# LedKeychain.net
KiCad netlist of a schematic drawn in EasyEDA Pro
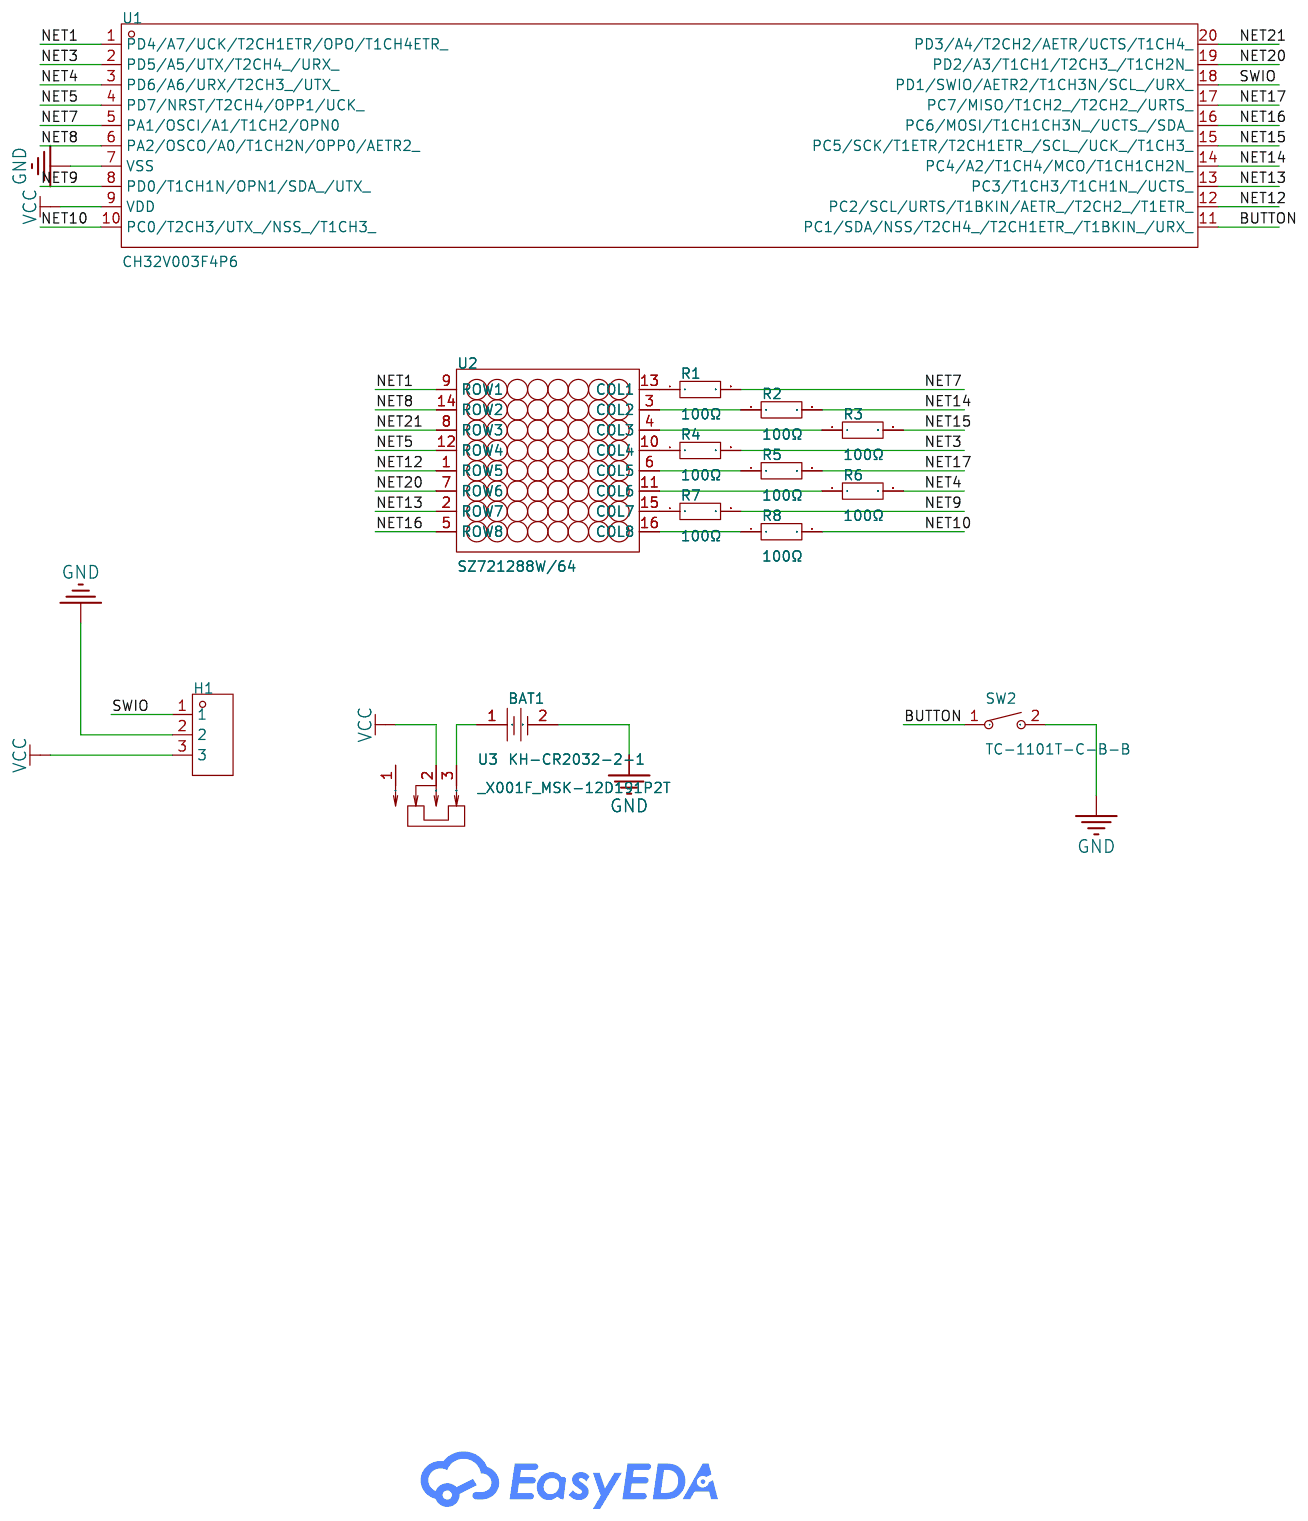
[diagram p0: schematic sheet]

(export (version "E")
  (design (tool "Eeschema 10.0.6"))
  (components
    (comp (ref "BAT1")
      (value "KH-CR2032-2-1")
      (footprint "easyedapro:BAT-TH_KH-CR2032-2-1")
      (fields (field (name "Manufacturer") "kinghelm(金航标)"))
      (libsource (lib "easyedapro") (part "KH-CR2032-2-1"))
    )
    (comp (ref "H1")
      (value "~")
      (footprint "easyedapro:HDR-TH_3P-P2.54-V-M")
      (libsource (lib "easyedapro") (part "PZ254V-11-03P_C2937625"))
    )
    (comp (ref "R1")
      (value "100Ω")
      (footprint "easyedapro:R0805")
      (fields
        (field (name "Manufacturer Part") "0805W8F1002T5E")
        (field (name "Manufacturer") "UNI-ROYAL(厚声)")
      )
      (libsource (lib "easyedapro") (part "0805W8F1002T5E"))
    )
    (comp (ref "R2")
      (value "100Ω")
      (footprint "easyedapro:R0805")
      (fields
        (field (name "Manufacturer Part") "0805W8F1002T5E")
        (field (name "Manufacturer") "UNI-ROYAL(厚声)")
      )
      (libsource (lib "easyedapro") (part "0805W8F1002T5E"))
    )
    (comp (ref "R3")
      (value "100Ω")
      (footprint "easyedapro:R0805")
      (fields
        (field (name "Manufacturer Part") "0805W8F1002T5E")
        (field (name "Manufacturer") "UNI-ROYAL(厚声)")
      )
      (libsource (lib "easyedapro") (part "0805W8F1002T5E"))
    )
    (comp (ref "R4")
      (value "100Ω")
      (footprint "easyedapro:R0805")
      (fields
        (field (name "Manufacturer Part") "0805W8F1002T5E")
        (field (name "Manufacturer") "UNI-ROYAL(厚声)")
      )
      (libsource (lib "easyedapro") (part "0805W8F1002T5E"))
    )
    (comp (ref "R5")
      (value "100Ω")
      (footprint "easyedapro:R0805")
      (fields
        (field (name "Manufacturer Part") "0805W8F1002T5E")
        (field (name "Manufacturer") "UNI-ROYAL(厚声)")
      )
      (libsource (lib "easyedapro") (part "0805W8F1002T5E"))
    )
    (comp (ref "R6")
      (value "100Ω")
      (footprint "easyedapro:R0805")
      (fields
        (field (name "Manufacturer Part") "0805W8F1002T5E")
        (field (name "Manufacturer") "UNI-ROYAL(厚声)")
      )
      (libsource (lib "easyedapro") (part "0805W8F1002T5E"))
    )
    (comp (ref "R7")
      (value "100Ω")
      (footprint "easyedapro:R0805")
      (fields
        (field (name "Manufacturer Part") "0805W8F1002T5E")
        (field (name "Manufacturer") "UNI-ROYAL(厚声)")
      )
      (libsource (lib "easyedapro") (part "0805W8F1002T5E"))
    )
    (comp (ref "R8")
      (value "100Ω")
      (footprint "easyedapro:R0805")
      (fields
        (field (name "Manufacturer Part") "0805W8F1002T5E")
        (field (name "Manufacturer") "UNI-ROYAL(厚声)")
      )
      (libsource (lib "easyedapro") (part "0805W8F1002T5E"))
    )
    (comp (ref "SW2")
      (value "TC-1101T-C-B-B")
      (footprint "easyedapro:KEY-TH_2P-L6.0-W3.5-P6.50")
      (fields (field (name "Manufacturer") "XKB Connectivity(中国星坤)"))
      (libsource (lib "easyedapro") (part "TC-1101T-C-B-B"))
    )
    (comp (ref "U1")
      (value "CH32V003F4P6")
      (footprint "easyedapro:TSSOP-20_L6.5-W4.4-P0.65-LS6.4-BL")
      (fields (field (name "Manufacturer") "WCH(南京沁恒)"))
      (libsource (lib "easyedapro") (part "CH32V003F4P6"))
    )
    (comp (ref "U2")
      (value "SZ721288W/64")
      (footprint "easyedapro:LED-SEG-TH_SZ421288N-64")
      (description "Dot Matrix Number:8x8 Emitting Color:White Polarity:Common Cathode")
      (fields (field (name "Manufacturer") "ARKLED(方舟)"))
      (libsource (lib "easyedapro") (part "SZ721288W/64"))
    )
    (comp (ref "U3")
      (value "_X001F_MSK-12D191P2T")
      (footprint "easyedapro:SW-TH_MSK-12D191P2T")
      (fields (field (name "Manufacturer Part") "_x001F_MSK-12D191P2T"))
      (libsource (lib "easyedapro") (part "MSK-12D19"))
    )
  )
  (nets
    (net (code "1") (name "/BUTTON") (class "Default")
      (node (ref "SW2") (pin "1") (pinfunction "1_1") (pintype "input"))
      (node (ref "U1") (pin "11") (pinfunction "PC1/SDA/NSS/T2CH4_/T2CH1ETR_/T1BKIN_/URX__11") (pintype "unspecified"))
    )
    (net (code "2") (name "/NET1") (class "Default")
      (node (ref "U1") (pin "1") (pinfunction "PD4/A7/UCK/T2CH1ETR/OPO/T1CH4ETR__1") (pintype "unspecified"))
      (node (ref "U2") (pin "9") (pinfunction "ROW1_9") (pintype "unspecified"))
    )
    (net (code "3") (name "/NET3") (class "Default")
      (node (ref "R4") (pin "2") (pinfunction "2_2") (pintype "input"))
      (node (ref "U1") (pin "2") (pinfunction "PD5/A5/UTX/T2CH4_/URX__2") (pintype "unspecified"))
    )
    (net (code "4") (name "/NET4") (class "Default")
      (node (ref "R6") (pin "2") (pinfunction "2_2") (pintype "input"))
      (node (ref "U1") (pin "3") (pinfunction "PD6/A6/URX/T2CH3_/UTX__3") (pintype "unspecified"))
    )
    (net (code "5") (name "/NET5") (class "Default")
      (node (ref "U1") (pin "4") (pinfunction "PD7/NRST/T2CH4/OPP1/UCK__4") (pintype "unspecified"))
      (node (ref "U2") (pin "12") (pinfunction "ROW4_12") (pintype "unspecified"))
    )
    (net (code "6") (name "/NET7") (class "Default")
      (node (ref "R1") (pin "2") (pinfunction "2_2") (pintype "input"))
      (node (ref "U1") (pin "5") (pinfunction "PA1/OSCI/A1/T1CH2/OPN0_5") (pintype "unspecified"))
    )
    (net (code "7") (name "/NET8") (class "Default")
      (node (ref "U1") (pin "6") (pinfunction "PA2/OSCO/A0/T1CH2N/OPP0/AETR2__6") (pintype "unspecified"))
      (node (ref "U2") (pin "14") (pinfunction "ROW2_14") (pintype "unspecified"))
    )
    (net (code "8") (name "/NET9") (class "Default")
      (node (ref "R7") (pin "2") (pinfunction "2_2") (pintype "input"))
      (node (ref "U1") (pin "8") (pinfunction "PD0/T1CH1N/OPN1/SDA_/UTX__8") (pintype "unspecified"))
    )
    (net (code "9") (name "/NET10") (class "Default")
      (node (ref "R8") (pin "2") (pinfunction "2_2") (pintype "input"))
      (node (ref "U1") (pin "10") (pinfunction "PC0/T2CH3/UTX_/NSS_/T1CH3__10") (pintype "unspecified"))
    )
    (net (code "10") (name "/NET12") (class "Default")
      (node (ref "U1") (pin "12") (pinfunction "PC2/SCL/URTS/T1BKIN/AETR_/T2CH2_/T1ETR__12") (pintype "unspecified"))
      (node (ref "U2") (pin "1") (pinfunction "ROW5_1") (pintype "unspecified"))
    )
    (net (code "11") (name "/NET13") (class "Default")
      (node (ref "U1") (pin "13") (pinfunction "PC3/T1CH3/T1CH1N_/UCTS__13") (pintype "unspecified"))
      (node (ref "U2") (pin "2") (pinfunction "ROW7_2") (pintype "unspecified"))
    )
    (net (code "12") (name "/NET14") (class "Default")
      (node (ref "R2") (pin "2") (pinfunction "2_2") (pintype "input"))
      (node (ref "U1") (pin "14") (pinfunction "PC4/A2/T1CH4/MCO/T1CH1CH2N__14") (pintype "unspecified"))
    )
    (net (code "13") (name "/NET15") (class "Default")
      (node (ref "R3") (pin "2") (pinfunction "2_2") (pintype "input"))
      (node (ref "U1") (pin "15") (pinfunction "PC5/SCK/T1ETR/T2CH1ETR_/SCL_/UCK_/T1CH3__15") (pintype "unspecified"))
    )
    (net (code "14") (name "/NET16") (class "Default")
      (node (ref "U1") (pin "16") (pinfunction "PC6/MOSI/T1CH1CH3N_/UCTS_/SDA__16") (pintype "unspecified"))
      (node (ref "U2") (pin "5") (pinfunction "ROW8_5") (pintype "unspecified"))
    )
    (net (code "15") (name "/NET17") (class "Default")
      (node (ref "R5") (pin "2") (pinfunction "2_2") (pintype "input"))
      (node (ref "U1") (pin "17") (pinfunction "PC7/MISO/T1CH2_/T2CH2_/URTS__17") (pintype "unspecified"))
    )
    (net (code "16") (name "/NET20") (class "Default")
      (node (ref "U1") (pin "19") (pinfunction "PD2/A3/T1CH1/T2CH3_/T1CH2N__19") (pintype "unspecified"))
      (node (ref "U2") (pin "7") (pinfunction "ROW6_7") (pintype "unspecified"))
    )
    (net (code "17") (name "/NET21") (class "Default")
      (node (ref "U1") (pin "20") (pinfunction "PD3/A4/T2CH2/AETR/UCTS/T1CH4__20") (pintype "unspecified"))
      (node (ref "U2") (pin "8") (pinfunction "ROW3_8") (pintype "unspecified"))
    )
    (net (code "18") (name "/SWIO") (class "Default")
      (node (ref "H1") (pin "1") (pinfunction "1_1") (pintype "unspecified"))
      (node (ref "U1") (pin "18") (pinfunction "PD1/SWIO/AETR2/T1CH3N/SCL_/URX__18") (pintype "unspecified"))
    )
    (net (code "19") (name "GND") (class "Default")
      (node (ref "BAT1") (pin "2") (pinfunction "2_2") (pintype "input"))
      (node (ref "H1") (pin "2") (pinfunction "2_2") (pintype "unspecified"))
      (node (ref "SW2") (pin "2") (pinfunction "2_2") (pintype "input"))
      (node (ref "U1") (pin "7") (pinfunction "VSS_7") (pintype "unspecified"))
    )
    (net (code "20") (name "Net-(BAT1-Pad1)") (class "Default")
      (node (ref "BAT1") (pin "1") (pinfunction "1_1") (pintype "input"))
      (node (ref "U3") (pin "3") (pinfunction "3_3") (pintype "unspecified"))
    )
    (net (code "21") (name "Net-(U2-COL1)") (class "Default")
      (node (ref "R1") (pin "1") (pinfunction "1_1") (pintype "input"))
      (node (ref "U2") (pin "13") (pinfunction "COL1_13") (pintype "unspecified"))
    )
    (net (code "22") (name "Net-(U2-COL2)") (class "Default")
      (node (ref "R2") (pin "1") (pinfunction "1_1") (pintype "input"))
      (node (ref "U2") (pin "3") (pinfunction "COL2_3") (pintype "unspecified"))
    )
    (net (code "23") (name "Net-(U2-COL3)") (class "Default")
      (node (ref "R3") (pin "1") (pinfunction "1_1") (pintype "input"))
      (node (ref "U2") (pin "4") (pinfunction "COL3_4") (pintype "unspecified"))
    )
    (net (code "24") (name "Net-(U2-COL4)") (class "Default")
      (node (ref "R4") (pin "1") (pinfunction "1_1") (pintype "input"))
      (node (ref "U2") (pin "10") (pinfunction "COL4_10") (pintype "unspecified"))
    )
    (net (code "25") (name "Net-(U2-COL5)") (class "Default")
      (node (ref "R5") (pin "1") (pinfunction "1_1") (pintype "input"))
      (node (ref "U2") (pin "6") (pinfunction "COL5_6") (pintype "unspecified"))
    )
    (net (code "26") (name "Net-(U2-COL6)") (class "Default")
      (node (ref "R6") (pin "1") (pinfunction "1_1") (pintype "input"))
      (node (ref "U2") (pin "11") (pinfunction "COL6_11") (pintype "unspecified"))
    )
    (net (code "27") (name "Net-(U2-COL7)") (class "Default")
      (node (ref "R7") (pin "1") (pinfunction "1_1") (pintype "input"))
      (node (ref "U2") (pin "15") (pinfunction "COL7_15") (pintype "unspecified"))
    )
    (net (code "28") (name "Net-(U2-COL8)") (class "Default")
      (node (ref "R8") (pin "1") (pinfunction "1_1") (pintype "input"))
      (node (ref "U2") (pin "16") (pinfunction "COL8_16") (pintype "unspecified"))
    )
    (net (code "29") (name "VCC") (class "Default")
      (node (ref "H1") (pin "3") (pinfunction "3_3") (pintype "unspecified"))
      (node (ref "U1") (pin "9") (pinfunction "VDD_9") (pintype "unspecified"))
      (node (ref "U3") (pin "2") (pinfunction "2_2") (pintype "unspecified"))
    )
    (net (code "30") (name "unconnected-(U3-Pad1)") (class "Default")
      (node (ref "U3") (pin "1") (pinfunction "1_1") (pintype "unspecified"))
    )
  )
)
